# p2_eth_rs232.net
KiCad netlist of a schematic drawn in Altium Designer
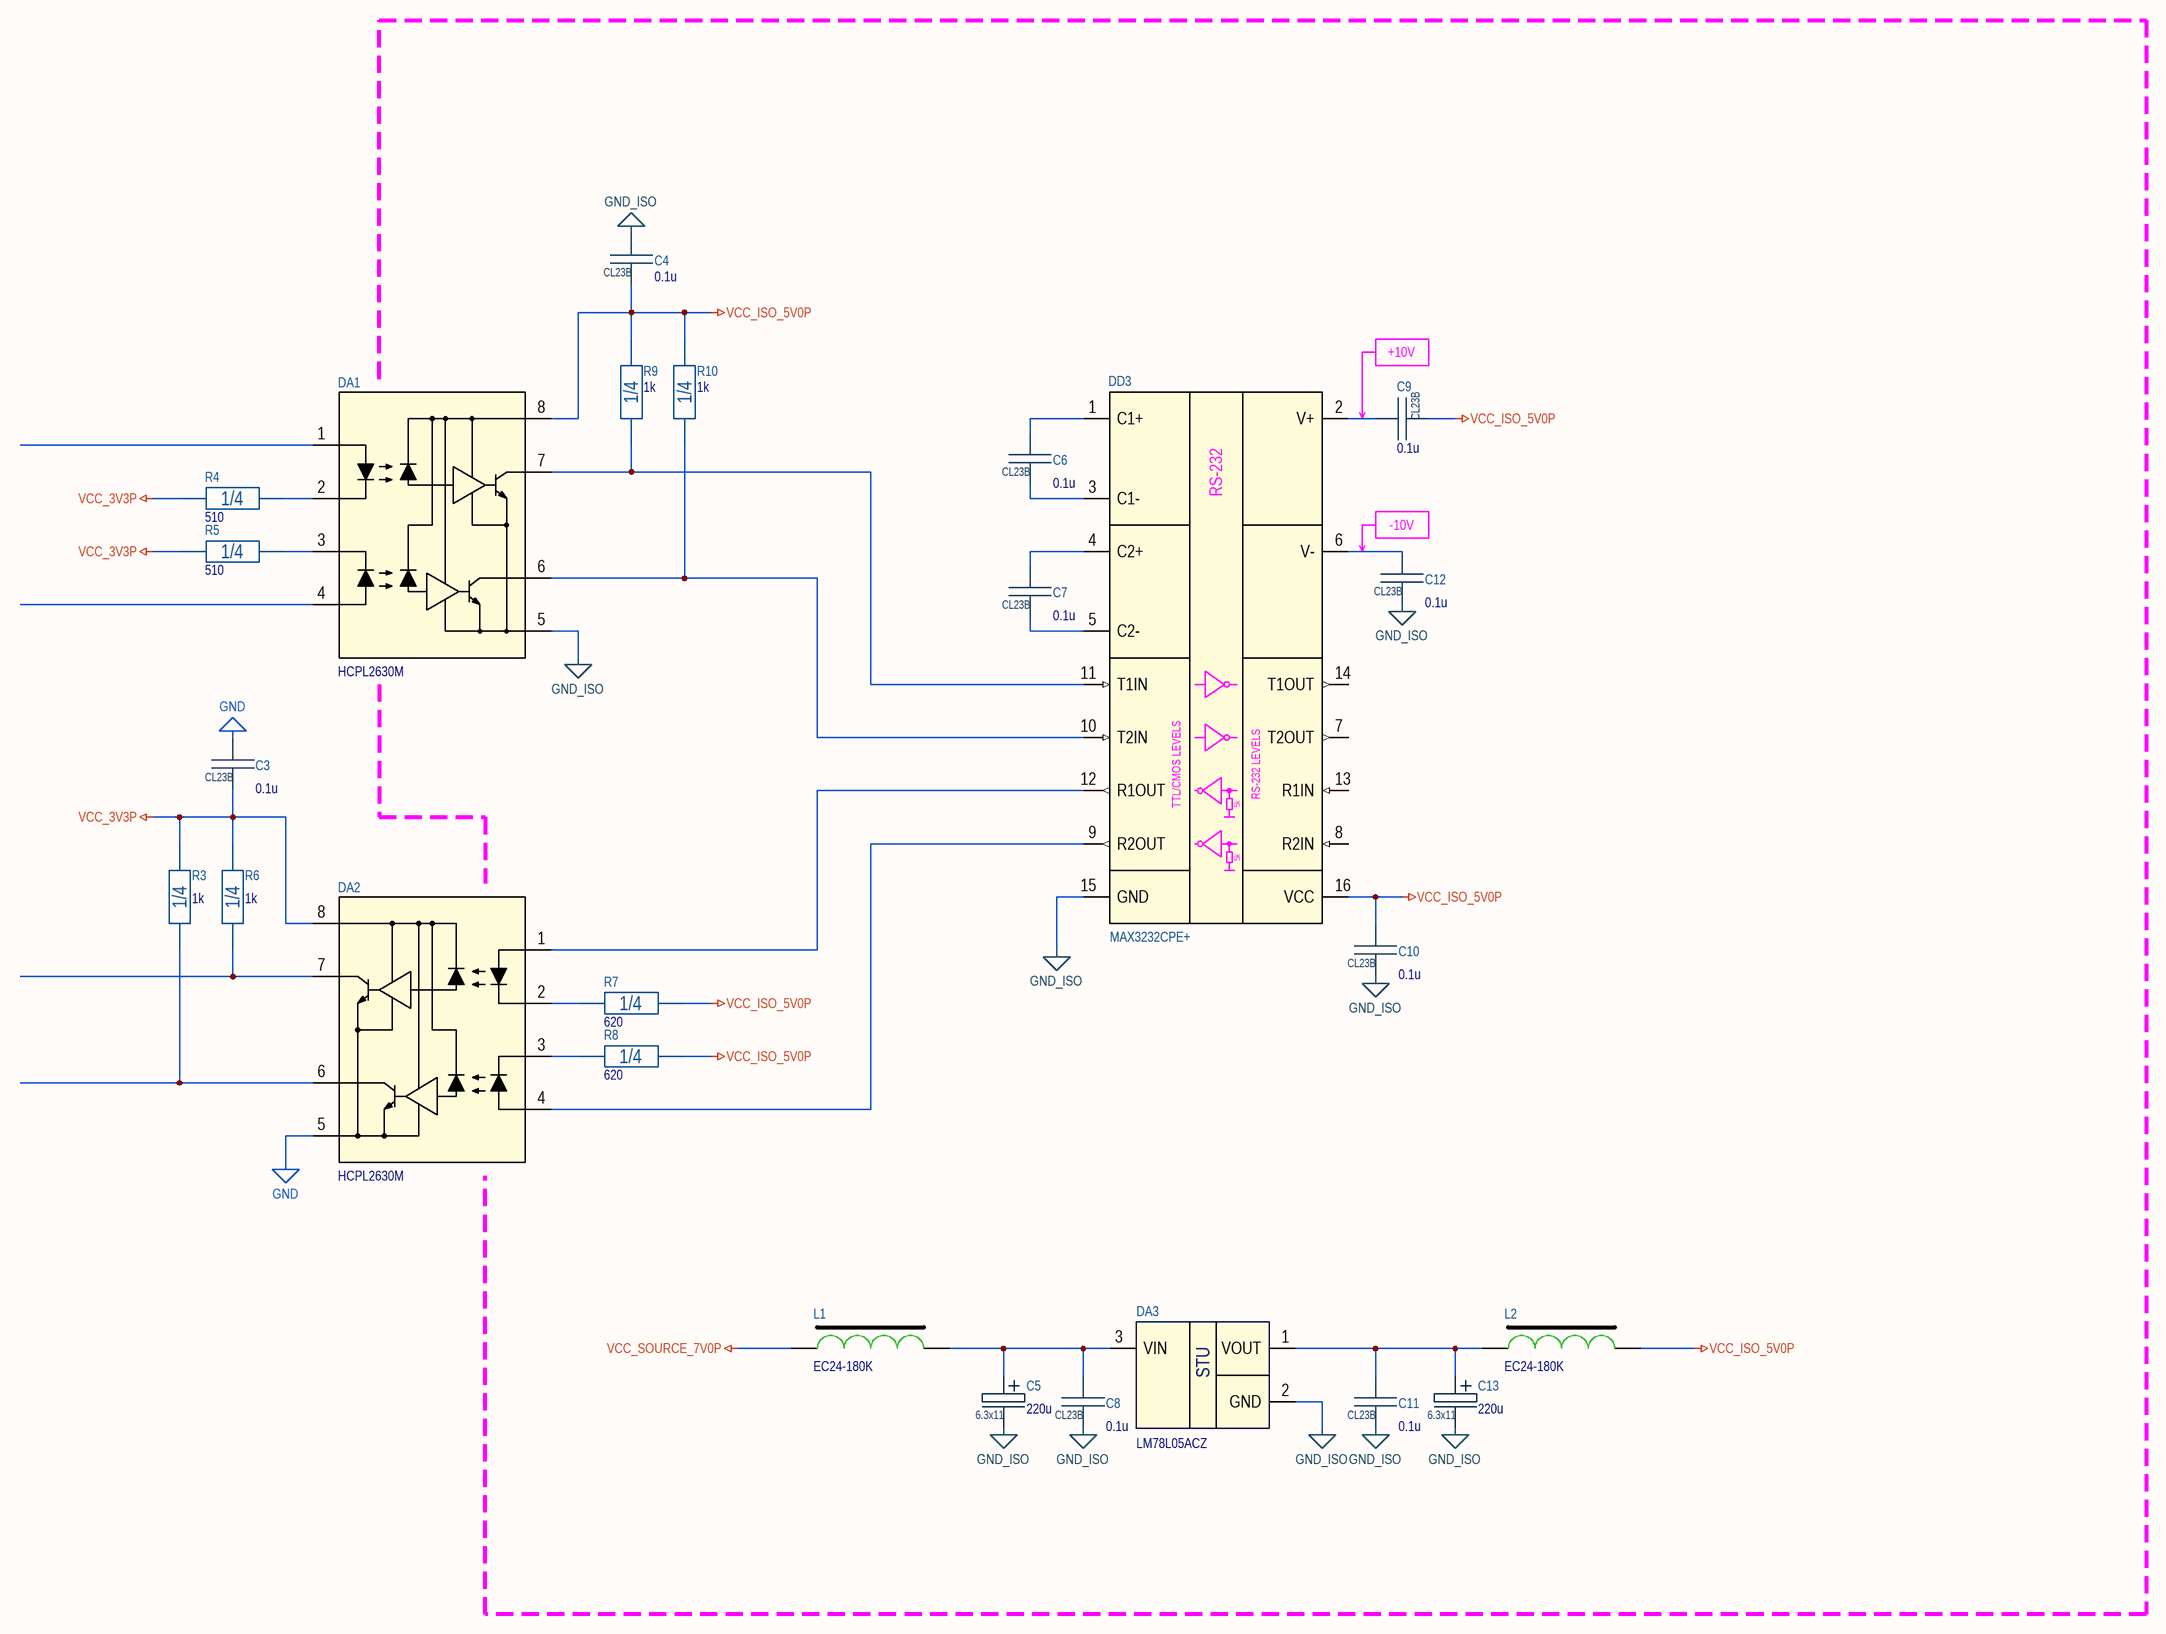
[diagram p0: p2_eth_rs232.SchDoc]

(export (version "E")
  (design (tool "Eeschema 10.0.6"))
  (components
    (comp (ref "C3")
      (value "0.1u")
      (footprint "PcbLib_RC:CL23B_7.2x2.5")
      (description "Box-type metallized polyester film capacitor")
      (fields
        (field (name "TOLERANCE") "± * %")
        (field (name "VOLTAGE") "63V")
        (field (name "PACKAGE") "CL23B")
      )
      (libsource (lib "Schlib_RC") (part "CL23B"))
    )
    (comp (ref "C4")
      (value "0.1u")
      (footprint "PcbLib_RC:CL23B_7.2x2.5")
      (description "Box-type metallized polyester film capacitor")
      (fields
        (field (name "TOLERANCE") "± * %")
        (field (name "VOLTAGE") "63V")
        (field (name "PACKAGE") "CL23B")
      )
      (libsource (lib "Schlib_RC") (part "CL23B"))
    )
    (comp (ref "C5")
      (value "220u")
      (footprint "PcbLib_RC:ECAP6.3X11X2.5_BRW")
      (description "Aluminium capacitor")
      (fields
        (field (name "TOLERANCE") "± 20 %")
        (field (name "VOLTAGE") "16V")
        (field (name "PACKAGE") "6.3x11")
      )
      (libsource (lib "Schlib_RC") (part "C_ECAP"))
    )
    (comp (ref "C6")
      (value "0.1u")
      (footprint "PcbLib_RC:CL23B_7.2x2.5")
      (description "Box-type metallized polyester film capacitor")
      (fields
        (field (name "TOLERANCE") "± * %")
        (field (name "VOLTAGE") "63V")
        (field (name "PACKAGE") "CL23B")
      )
      (libsource (lib "Schlib_RC") (part "CL23B"))
    )
    (comp (ref "C7")
      (value "0.1u")
      (footprint "PcbLib_RC:CL23B_7.2x2.5")
      (description "Box-type metallized polyester film capacitor")
      (fields
        (field (name "TOLERANCE") "± * %")
        (field (name "VOLTAGE") "63V")
        (field (name "PACKAGE") "CL23B")
      )
      (libsource (lib "Schlib_RC") (part "CL23B"))
    )
    (comp (ref "C8")
      (value "0.1u")
      (footprint "PcbLib_RC:CL23B_7.2x2.5")
      (description "Box-type metallized polyester film capacitor")
      (fields
        (field (name "TOLERANCE") "± * %")
        (field (name "VOLTAGE") "63V")
        (field (name "PACKAGE") "CL23B")
      )
      (libsource (lib "Schlib_RC") (part "CL23B"))
    )
    (comp (ref "C9")
      (value "0.1u")
      (footprint "PcbLib_RC:CL23B_7.2x2.5")
      (description "Box-type metallized polyester film capacitor")
      (fields
        (field (name "TOLERANCE") "± * %")
        (field (name "VOLTAGE") "63V")
        (field (name "PACKAGE") "CL23B")
      )
      (libsource (lib "Schlib_RC") (part "CL23B"))
    )
    (comp (ref "C10")
      (value "0.1u")
      (footprint "PcbLib_RC:CL23B_7.2x2.5")
      (description "Box-type metallized polyester film capacitor")
      (fields
        (field (name "TOLERANCE") "± * %")
        (field (name "VOLTAGE") "63V")
        (field (name "PACKAGE") "CL23B")
      )
      (libsource (lib "Schlib_RC") (part "CL23B"))
    )
    (comp (ref "C11")
      (value "0.1u")
      (footprint "PcbLib_RC:CL23B_7.2x2.5")
      (description "Box-type metallized polyester film capacitor")
      (fields
        (field (name "TOLERANCE") "± * %")
        (field (name "VOLTAGE") "63V")
        (field (name "PACKAGE") "CL23B")
      )
      (libsource (lib "Schlib_RC") (part "CL23B"))
    )
    (comp (ref "C12")
      (value "0.1u")
      (footprint "PcbLib_RC:CL23B_7.2x2.5")
      (description "Box-type metallized polyester film capacitor")
      (fields
        (field (name "TOLERANCE") "± * %")
        (field (name "VOLTAGE") "63V")
        (field (name "PACKAGE") "CL23B")
      )
      (libsource (lib "Schlib_RC") (part "CL23B"))
    )
    (comp (ref "C13")
      (value "220u")
      (footprint "PcbLib_RC:ECAP6.3X11X2.5_BRW")
      (description "Aluminium capacitor")
      (fields
        (field (name "TOLERANCE") "± 20 %")
        (field (name "VOLTAGE") "16V")
        (field (name "PACKAGE") "6.3x11")
      )
      (libsource (lib "Schlib_RC") (part "C_ECAP"))
    )
    (comp (ref "DA1")
      (value "HCPL2630M")
      (footprint "PcbLib_ICs:DIP-8P-M01")
      (description "Dual-Channel High-Speed 10 MBit/s Logic Gate Optocouplers")
      (fields (field (name "MANUFACTURER") "ON Semiconductor"))
      (libsource (lib "Schlib_ONSemiconductor") (part "HCPL2630M"))
    )
    (comp (ref "DA2")
      (value "HCPL2630M")
      (footprint "PcbLib_ICs:DIP-8P-M01")
      (description "Dual-Channel High-Speed 10 MBit/s Logic Gate Optocouplers")
      (fields (field (name "MANUFACTURER") "ON Semiconductor"))
      (libsource (lib "Schlib_ONSemiconductor") (part "HCPL2630M"))
    )
    (comp (ref "DA3")
      (value "LM78L05ACZ")
      (footprint "PcbLib_ICs:TO-92 (VERTICAL,LINE)")
      (description "100-mA Fixed Output Linear Regulator")
      (fields (field (name "MANUFACTURER") "Texas Instruments"))
      (libsource (lib "Schlib_Texas_Instruments") (part "LM78L05ACZ"))
    )
    (comp (ref "DD3")
      (value "MAX3232CPE+")
      (footprint "PcbLib_ICs:DIP-16P-M03")
      (description "3.0V to 5.5V, Low-Power, Up to 1Mbps, True RS-232 Transceivers")
      (fields (field (name "MANUFACTURER") "Maxim Integrated"))
      (libsource (lib "Schlib_Maxim_Integrated") (part "MAX3232CPE+"))
    )
    (comp (ref "L1")
      (value "EC24-180K")
      (footprint "PcbLib_RC:EC24_GREEN")
      (description "Axial leaded coated inductors")
      (fields (field (name "MANUFACTURER") "3L Electronic"))
      (libsource (lib "Schlib_RC") (part "EC24"))
    )
    (comp (ref "L2")
      (value "EC24-180K")
      (footprint "PcbLib_RC:EC24_GREEN")
      (description "Axial leaded coated inductors")
      (fields (field (name "MANUFACTURER") "3L Electronic"))
      (libsource (lib "Schlib_RC") (part "EC24"))
    )
    (comp (ref "R3")
      (value "1k")
      (footprint "PcbLib_RC:CFR-25")
      (description "Resistor 1/4W")
      (fields
        (field (name "TOLERANCE") "± 1 %")
        (field (name "PART NUMBER") "MFR-25FTF52-1K")
        (field (name "PACKAGE") "1/4")
      )
      (libsource (lib "Schlib_RC") (part "CF25"))
    )
    (comp (ref "R4")
      (value "510")
      (footprint "PcbLib_RC:CFR-25")
      (description "Resistor 1/4W")
      (fields
        (field (name "TOLERANCE") "± 1 %")
        (field (name "PART NUMBER") "MFR-25FTF52-510R")
        (field (name "PACKAGE") "1/4")
      )
      (libsource (lib "Schlib_RC") (part "CF25"))
    )
    (comp (ref "R5")
      (value "510")
      (footprint "PcbLib_RC:CFR-25")
      (description "Resistor 1/4W")
      (fields
        (field (name "TOLERANCE") "± 1 %")
        (field (name "PART NUMBER") "MFR-25FTF52-510R")
        (field (name "PACKAGE") "1/4")
      )
      (libsource (lib "Schlib_RC") (part "CF25"))
    )
    (comp (ref "R6")
      (value "1k")
      (footprint "PcbLib_RC:CFR-25")
      (description "Resistor 1/4W")
      (fields
        (field (name "TOLERANCE") "± 1 %")
        (field (name "PART NUMBER") "MFR-25FTF52-1K")
        (field (name "PACKAGE") "1/4")
      )
      (libsource (lib "Schlib_RC") (part "CF25"))
    )
    (comp (ref "R7")
      (value "620")
      (footprint "PcbLib_RC:CFR-25")
      (description "Resistor 1/4W")
      (fields
        (field (name "TOLERANCE") "± 1 %")
        (field (name "PART NUMBER") "MFR-25FTF52-620R")
        (field (name "PACKAGE") "1/4")
      )
      (libsource (lib "Schlib_RC") (part "CF25"))
    )
    (comp (ref "R8")
      (value "620")
      (footprint "PcbLib_RC:CFR-25")
      (description "Resistor 1/4W")
      (fields
        (field (name "TOLERANCE") "± 1 %")
        (field (name "PART NUMBER") "MFR-25FTF52-620R")
        (field (name "PACKAGE") "1/4")
      )
      (libsource (lib "Schlib_RC") (part "CF25"))
    )
    (comp (ref "R9")
      (value "1k")
      (footprint "PcbLib_RC:CFR-25")
      (description "Resistor 1/4W")
      (fields
        (field (name "TOLERANCE") "± 1 %")
        (field (name "PART NUMBER") "MFR-25FTF52-1K")
        (field (name "PACKAGE") "1/4")
      )
      (libsource (lib "Schlib_RC") (part "CF25"))
    )
    (comp (ref "R10")
      (value "1k")
      (footprint "PcbLib_RC:CFR-25")
      (description "Resistor 1/4W")
      (fields
        (field (name "TOLERANCE") "± 1 %")
        (field (name "PART NUMBER") "MFR-25FTF52-1K")
        (field (name "PACKAGE") "1/4")
      )
      (libsource (lib "Schlib_RC") (part "CF25"))
    )
  )
  (nets
    (net (code "1") (name "GND") (class "Default")
      (node (ref "C3") (pin "1") (pinfunction "1_1") (pintype "passive"))
      (node (ref "DA2") (pin "5") (pinfunction "GND_5") (pintype "passive"))
    )
    (net (code "2") (name "GND_ISO") (class "Default")
      (node (ref "C10") (pin "2") (pinfunction "2_2") (pintype "passive"))
      (node (ref "C11") (pin "2") (pinfunction "2_2") (pintype "passive"))
      (node (ref "C12") (pin "2") (pinfunction "2_2") (pintype "passive"))
      (node (ref "C13") (pin "2") (pinfunction "2_2") (pintype "passive"))
      (node (ref "C4") (pin "1") (pinfunction "1_1") (pintype "passive"))
      (node (ref "C5") (pin "2") (pinfunction "2_2") (pintype "passive"))
      (node (ref "C8") (pin "2") (pinfunction "2_2") (pintype "passive"))
      (node (ref "DA1") (pin "5") (pinfunction "GND_5") (pintype "passive"))
      (node (ref "DA3") (pin "2") (pinfunction "GND_2") (pintype "power_in"))
      (node (ref "DD3") (pin "15") (pinfunction "GND_15") (pintype "power_in"))
    )
    (net (code "3") (name "Net-(DA1-CATHODE1)") (class "Default")
      (node (ref "DA1") (pin "2") (pinfunction "CATHODE1_2") (pintype "power_in"))
      (node (ref "R4") (pin "2") (pinfunction "2_2") (pintype "passive"))
    )
    (net (code "4") (name "Net-(DA1-CATHODE2)") (class "Default")
      (node (ref "DA1") (pin "3") (pinfunction "CATHODE2_3") (pintype "power_in"))
      (node (ref "R5") (pin "2") (pinfunction "2_2") (pintype "passive"))
    )
    (net (code "5") (name "Net-(DA1-V01)") (class "Default")
      (node (ref "DA1") (pin "7") (pinfunction "V01_7") (pintype "passive"))
      (node (ref "DD3") (pin "11") (pinfunction "T1IN_11") (pintype "input"))
      (node (ref "R9") (pin "2") (pinfunction "2_2") (pintype "passive"))
    )
    (net (code "6") (name "Net-(DA1-V02)") (class "Default")
      (node (ref "DA1") (pin "6") (pinfunction "V02_6") (pintype "passive"))
      (node (ref "DD3") (pin "10") (pinfunction "T2IN_10") (pintype "input"))
      (node (ref "R10") (pin "2") (pinfunction "2_2") (pintype "passive"))
    )
    (net (code "7") (name "Net-(DA2-ANODE1)") (class "Default")
      (node (ref "DA2") (pin "1") (pinfunction "ANODE1_1") (pintype "passive"))
      (node (ref "DD3") (pin "12") (pinfunction "R1OUT_12") (pintype "output"))
    )
    (net (code "8") (name "Net-(DA2-ANODE2)") (class "Default")
      (node (ref "DA2") (pin "4") (pinfunction "ANODE2_4") (pintype "passive"))
      (node (ref "DD3") (pin "9") (pinfunction "R2OUT_9") (pintype "output"))
    )
    (net (code "9") (name "Net-(DA2-CATHODE1)") (class "Default")
      (node (ref "DA2") (pin "2") (pinfunction "CATHODE1_2") (pintype "power_in"))
      (node (ref "R7") (pin "2") (pinfunction "2_2") (pintype "passive"))
    )
    (net (code "10") (name "Net-(DA2-CATHODE2)") (class "Default")
      (node (ref "DA2") (pin "3") (pinfunction "CATHODE2_3") (pintype "power_in"))
      (node (ref "R8") (pin "2") (pinfunction "2_2") (pintype "passive"))
    )
    (net (code "11") (name "Net-(DA2-V01)") (class "Default")
      (node (ref "DA2") (pin "7") (pinfunction "V01_7") (pintype "passive"))
      (node (ref "R6") (pin "2") (pinfunction "2_2") (pintype "passive"))
    )
    (net (code "12") (name "Net-(DA2-V02)") (class "Default")
      (node (ref "DA2") (pin "6") (pinfunction "V02_6") (pintype "passive"))
      (node (ref "R3") (pin "2") (pinfunction "2_2") (pintype "passive"))
    )
    (net (code "13") (name "Net-(DA3-VIN)") (class "Default")
      (node (ref "C5") (pin "1") (pinfunction "1_1") (pintype "passive"))
      (node (ref "C8") (pin "1") (pinfunction "1_1") (pintype "passive"))
      (node (ref "DA3") (pin "3") (pinfunction "VIN_3") (pintype "power_in"))
      (node (ref "L1") (pin "2") (pinfunction "2_2") (pintype "passive"))
    )
    (net (code "14") (name "Net-(DA3-VOUT)") (class "Default")
      (node (ref "C11") (pin "1") (pinfunction "1_1") (pintype "passive"))
      (node (ref "C13") (pin "1") (pinfunction "1_1") (pintype "passive"))
      (node (ref "DA3") (pin "1") (pinfunction "VOUT_1") (pintype "power_in"))
      (node (ref "L2") (pin "1") (pinfunction "1_1") (pintype "passive"))
    )
    (net (code "15") (name "Net-(DD3-C1+)") (class "Default")
      (node (ref "C6") (pin "1") (pinfunction "1_1") (pintype "passive"))
      (node (ref "DD3") (pin "1") (pinfunction "C1+_1") (pintype "passive"))
    )
    (net (code "16") (name "Net-(DD3-C1-)") (class "Default")
      (node (ref "C6") (pin "2") (pinfunction "2_2") (pintype "passive"))
      (node (ref "DD3") (pin "3") (pinfunction "C1-_3") (pintype "passive"))
    )
    (net (code "17") (name "Net-(DD3-C2+)") (class "Default")
      (node (ref "C7") (pin "1") (pinfunction "1_1") (pintype "passive"))
      (node (ref "DD3") (pin "4") (pinfunction "C2+_4") (pintype "passive"))
    )
    (net (code "18") (name "Net-(DD3-C2-)") (class "Default")
      (node (ref "C7") (pin "2") (pinfunction "2_2") (pintype "passive"))
      (node (ref "DD3") (pin "5") (pinfunction "C2-_5") (pintype "passive"))
    )
    (net (code "19") (name "Net-(DD3-V+)") (class "Default")
      (node (ref "C9") (pin "1") (pinfunction "1_1") (pintype "passive"))
      (node (ref "DD3") (pin "2") (pinfunction "V+_2") (pintype "passive"))
    )
    (net (code "20") (name "Net-(DD3-V-)") (class "Default")
      (node (ref "C12") (pin "1") (pinfunction "1_1") (pintype "passive"))
      (node (ref "DD3") (pin "6") (pinfunction "V-_6") (pintype "passive"))
    )
    (net (code "21") (name "VCC_3V3P") (class "Default")
      (node (ref "C3") (pin "2") (pinfunction "2_2") (pintype "passive"))
      (node (ref "DA2") (pin "8") (pinfunction "VCC_8") (pintype "power_in"))
      (node (ref "R3") (pin "1") (pinfunction "1_1") (pintype "passive"))
      (node (ref "R4") (pin "1") (pinfunction "1_1") (pintype "passive"))
      (node (ref "R5") (pin "1") (pinfunction "1_1") (pintype "passive"))
      (node (ref "R6") (pin "1") (pinfunction "1_1") (pintype "passive"))
    )
    (net (code "22") (name "VCC_ISO_5V0P") (class "Default")
      (node (ref "C10") (pin "1") (pinfunction "1_1") (pintype "passive"))
      (node (ref "C4") (pin "2") (pinfunction "2_2") (pintype "passive"))
      (node (ref "C9") (pin "2") (pinfunction "2_2") (pintype "passive"))
      (node (ref "DA1") (pin "8") (pinfunction "VCC_8") (pintype "power_in"))
      (node (ref "DD3") (pin "16") (pinfunction "VCC_16") (pintype "power_in"))
      (node (ref "L2") (pin "2") (pinfunction "2_2") (pintype "passive"))
      (node (ref "R10") (pin "1") (pinfunction "1_1") (pintype "passive"))
      (node (ref "R7") (pin "1") (pinfunction "1_1") (pintype "passive"))
      (node (ref "R8") (pin "1") (pinfunction "1_1") (pintype "passive"))
      (node (ref "R9") (pin "1") (pinfunction "1_1") (pintype "passive"))
    )
    (net (code "23") (name "VCC_SOURCE_7V0P") (class "Default")
      (node (ref "L1") (pin "1") (pinfunction "1_1") (pintype "passive"))
    )
    (net (code "24") (name "unconnected-(DA1-ANODE1-Pad1)") (class "Default")
      (node (ref "DA1") (pin "1") (pinfunction "ANODE1_1") (pintype "passive"))
    )
    (net (code "25") (name "unconnected-(DA1-ANODE2-Pad4)") (class "Default")
      (node (ref "DA1") (pin "4") (pinfunction "ANODE2_4") (pintype "passive"))
    )
    (net (code "26") (name "unconnected-(DD3-R1IN-Pad13)") (class "Default")
      (node (ref "DD3") (pin "13") (pinfunction "R1IN_13") (pintype "input"))
    )
    (net (code "27") (name "unconnected-(DD3-R2IN-Pad8)") (class "Default")
      (node (ref "DD3") (pin "8") (pinfunction "R2IN_8") (pintype "input"))
    )
    (net (code "28") (name "unconnected-(DD3-T1OUT-Pad14)") (class "Default")
      (node (ref "DD3") (pin "14") (pinfunction "T1OUT_14") (pintype "output"))
    )
    (net (code "29") (name "unconnected-(DD3-T2OUT-Pad7)") (class "Default")
      (node (ref "DD3") (pin "7") (pinfunction "T2OUT_7") (pintype "output"))
    )
  )
)
